# PCB_Schematic_Smart_Home.net
KiCad netlist of a schematic drawn in EasyEDA
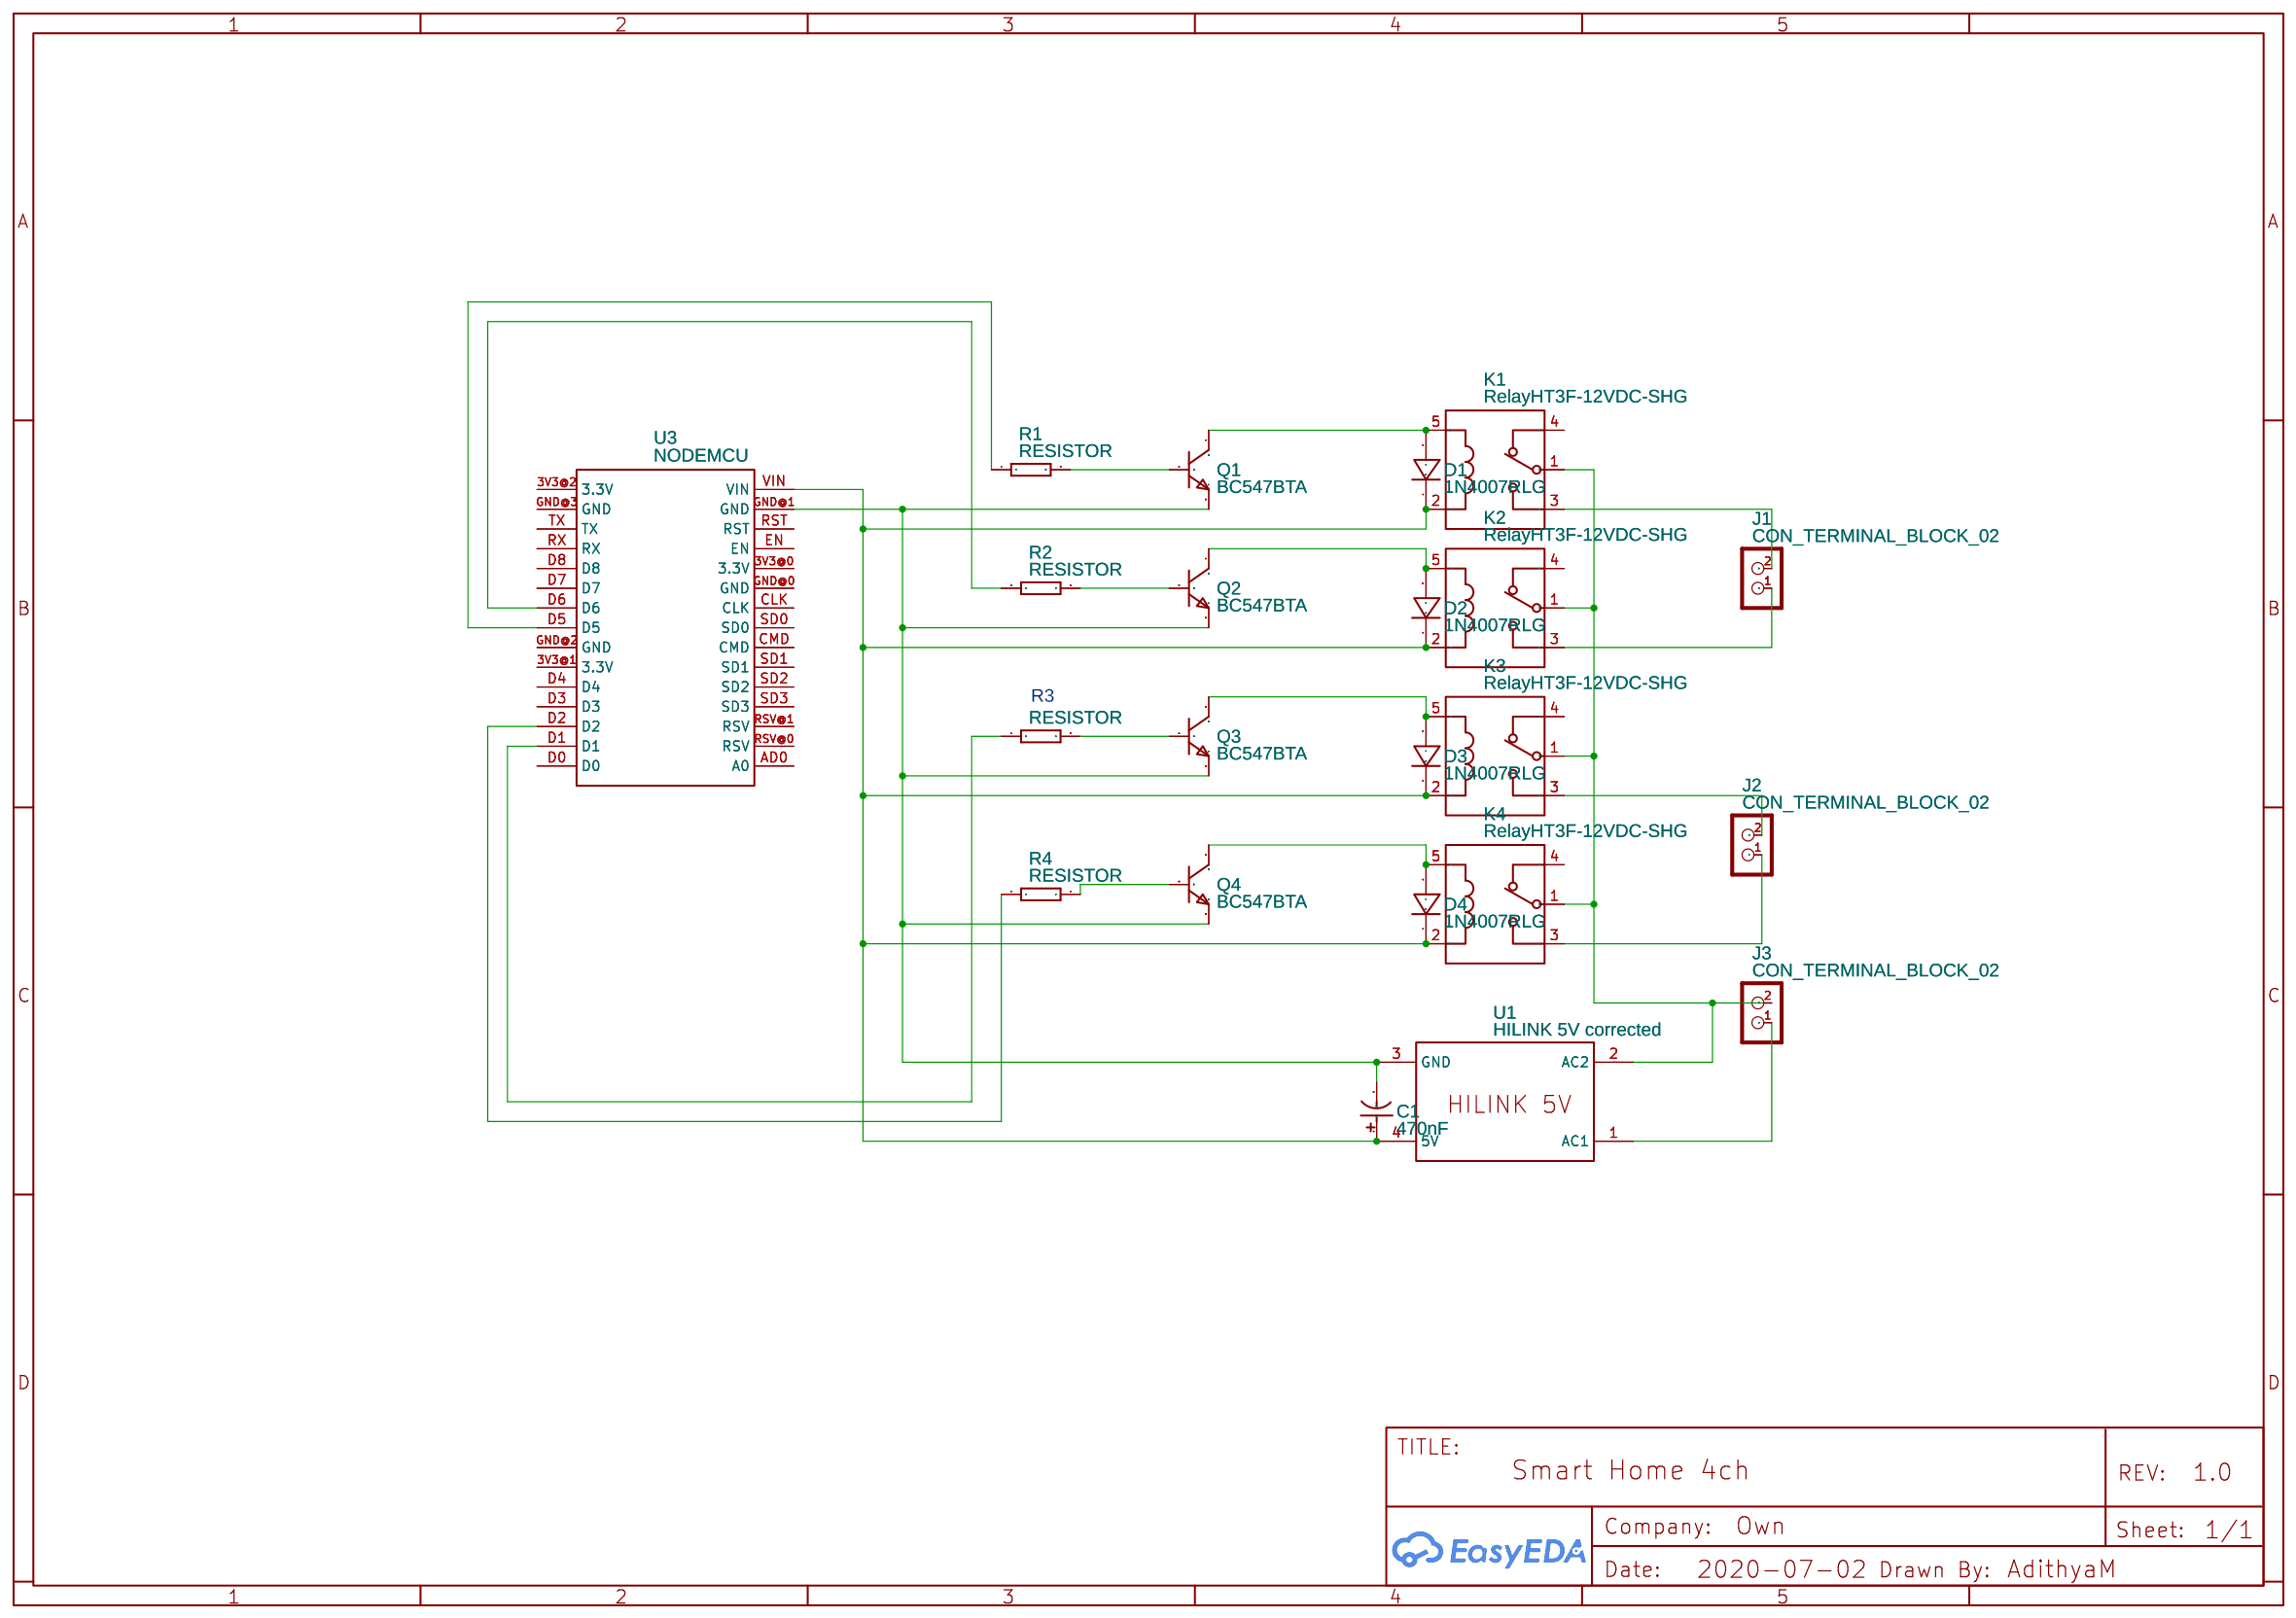
[diagram p0: schematic sheet]

(export (version "E")
  (design (tool "Eeschema 10.0.6"))
  (components
    (comp (ref "C1")
      (value "470nF")
      (fields
        (field (name "BOM_Manufacturer Part") "0.47uF 50V 4*5")
        (field (name "BOM_Supplier Part") "C45095")
      )
      (libsource (lib "") (part "0.47uF_50V_mz"))
    )
    (comp (ref "D1")
      (value "1N4007RLG")
      (fields (field (name "BOM_Supplier Part") "C53568"))
      (libsource (lib "") (part "1N4007RLG"))
    )
    (comp (ref "D2")
      (value "1N4007RLG")
      (fields (field (name "BOM_Supplier Part") "C53568"))
      (libsource (lib "") (part "1N4007RLG"))
    )
    (comp (ref "D3")
      (value "1N4007RLG")
      (fields (field (name "BOM_Supplier Part") "C53568"))
      (libsource (lib "") (part "1N4007RLG"))
    )
    (comp (ref "D4")
      (value "1N4007RLG")
      (fields (field (name "BOM_Supplier Part") "C53568"))
      (libsource (lib "") (part "1N4007RLG"))
    )
    (comp (ref "J1") (value "CON_TERMINAL_BLOCK_02") (libsource (lib "") (part "CON_TERMINAL_BLOCK_02")))
    (comp (ref "J2") (value "CON_TERMINAL_BLOCK_02") (libsource (lib "") (part "CON_TERMINAL_BLOCK_02")))
    (comp (ref "J3") (value "CON_TERMINAL_BLOCK_02") (libsource (lib "") (part "CON_TERMINAL_BLOCK_02")))
    (comp (ref "K1")
      (value "RelayHT3F-12VDC-SHG")
      (fields (field (name "BOM_Supplier Part") "C22022"))
      (libsource (lib "") (part "RelayHT3F-12VDC-SHG"))
    )
    (comp (ref "K2")
      (value "RelayHT3F-12VDC-SHG")
      (fields (field (name "BOM_Supplier Part") "C22022"))
      (libsource (lib "") (part "RelayHT3F-12VDC-SHG"))
    )
    (comp (ref "K3")
      (value "RelayHT3F-12VDC-SHG")
      (fields (field (name "BOM_Supplier Part") "C22022"))
      (libsource (lib "") (part "RelayHT3F-12VDC-SHG"))
    )
    (comp (ref "K4")
      (value "RelayHT3F-12VDC-SHG")
      (fields (field (name "BOM_Supplier Part") "C22022"))
      (libsource (lib "") (part "RelayHT3F-12VDC-SHG"))
    )
    (comp (ref "Q1")
      (value "BC547BTA")
      (fields (field (name "BOM_Supplier Part") "C258144"))
      (libsource (lib "") (part "BC547BTA"))
    )
    (comp (ref "Q2")
      (value "BC547BTA")
      (fields (field (name "BOM_Supplier Part") "C258144"))
      (libsource (lib "") (part "BC547BTA"))
    )
    (comp (ref "Q3")
      (value "BC547BTA")
      (fields (field (name "BOM_Supplier Part") "C258144"))
      (libsource (lib "") (part "BC547BTA"))
    )
    (comp (ref "Q4")
      (value "BC547BTA")
      (fields (field (name "BOM_Supplier Part") "C258144"))
      (libsource (lib "") (part "BC547BTA"))
    )
    (comp (ref "R1") (value "RESISTOR") (libsource (lib "") (part "RESISTOR")))
    (comp (ref "R2") (value "RESISTOR") (libsource (lib "") (part "RESISTOR")))
    (comp (ref "R3") (value "RESISTOR") (libsource (lib "") (part "RESISTOR")))
    (comp (ref "R4") (value "RESISTOR") (libsource (lib "") (part "RESISTOR")))
    (comp (ref "U1")
      (value "HILINK 5V corrected")
      (fields (field (name "BOM_Manufacturer Part") "HILINK 5V"))
      (libsource (lib "") (part "HILINK 5V corrected"))
    )
    (comp (ref "U3") (value "NODEMCU") (libsource (lib "") (part "NODEMCU")))
  )
  (nets
    (net (code "1") (name "Net-(D1-A)") (class "Default")
      (node (ref "D1") (pin "2") (pinfunction "A_2") (pintype "unspecified"))
      (node (ref "K1") (pin "5") (pinfunction "5_5") (pintype "unspecified"))
      (node (ref "Q1") (pin "1") (pinfunction "C_1") (pintype "unspecified"))
    )
    (net (code "2") (name "Net-(D1-C)") (class "Default")
      (node (ref "C1") (pin "1") (pinfunction "1_1") (pintype "input"))
      (node (ref "D1") (pin "1") (pinfunction "C_1") (pintype "unspecified"))
      (node (ref "D2") (pin "1") (pinfunction "C_1") (pintype "unspecified"))
      (node (ref "D3") (pin "1") (pinfunction "C_1") (pintype "unspecified"))
      (node (ref "D4") (pin "1") (pinfunction "C_1") (pintype "unspecified"))
      (node (ref "K1") (pin "2") (pinfunction "2_2") (pintype "unspecified"))
      (node (ref "K2") (pin "2") (pinfunction "2_2") (pintype "unspecified"))
      (node (ref "K3") (pin "2") (pinfunction "2_2") (pintype "unspecified"))
      (node (ref "K4") (pin "2") (pinfunction "2_2") (pintype "unspecified"))
      (node (ref "U1") (pin "4") (pinfunction "5V_4") (pintype "unspecified"))
      (node (ref "U3") (pin "VIN") (pinfunction "VIN_VIN") (pintype "unspecified"))
    )
    (net (code "3") (name "Net-(D2-A)") (class "Default")
      (node (ref "D2") (pin "2") (pinfunction "A_2") (pintype "unspecified"))
      (node (ref "K2") (pin "5") (pinfunction "5_5") (pintype "unspecified"))
      (node (ref "Q2") (pin "1") (pinfunction "C_1") (pintype "unspecified"))
    )
    (net (code "4") (name "Net-(D3-A)") (class "Default")
      (node (ref "D3") (pin "2") (pinfunction "A_2") (pintype "unspecified"))
      (node (ref "K3") (pin "5") (pinfunction "5_5") (pintype "unspecified"))
      (node (ref "Q3") (pin "1") (pinfunction "C_1") (pintype "unspecified"))
    )
    (net (code "5") (name "Net-(D4-A)") (class "Default")
      (node (ref "D4") (pin "2") (pinfunction "A_2") (pintype "unspecified"))
      (node (ref "K4") (pin "5") (pinfunction "5_5") (pintype "unspecified"))
      (node (ref "Q4") (pin "1") (pinfunction "C_1") (pintype "unspecified"))
    )
    (net (code "6") (name "Net-(J1-Pad1)") (class "Default")
      (node (ref "J1") (pin "1") (pinfunction "1_1") (pintype "unspecified"))
      (node (ref "K2") (pin "3") (pinfunction "3_3") (pintype "unspecified"))
    )
    (net (code "7") (name "Net-(J1-Pad2)") (class "Default")
      (node (ref "J1") (pin "2") (pinfunction "2_2") (pintype "unspecified"))
      (node (ref "K1") (pin "3") (pinfunction "3_3") (pintype "unspecified"))
    )
    (net (code "8") (name "Net-(J2-Pad1)") (class "Default")
      (node (ref "J2") (pin "1") (pinfunction "1_1") (pintype "unspecified"))
      (node (ref "K4") (pin "3") (pinfunction "3_3") (pintype "unspecified"))
    )
    (net (code "9") (name "Net-(J2-Pad2)") (class "Default")
      (node (ref "J2") (pin "2") (pinfunction "2_2") (pintype "unspecified"))
      (node (ref "K3") (pin "3") (pinfunction "3_3") (pintype "unspecified"))
    )
    (net (code "10") (name "Net-(Q1-B)") (class "Default")
      (node (ref "Q1") (pin "2") (pinfunction "B_2") (pintype "unspecified"))
      (node (ref "R1") (pin "2") (pinfunction "2_2") (pintype "unspecified"))
    )
    (net (code "11") (name "Net-(Q1-E)") (class "Default")
      (node (ref "C1") (pin "2") (pinfunction "2_2") (pintype "input"))
      (node (ref "Q1") (pin "3") (pinfunction "E_3") (pintype "unspecified"))
      (node (ref "Q2") (pin "3") (pinfunction "E_3") (pintype "unspecified"))
      (node (ref "Q3") (pin "3") (pinfunction "E_3") (pintype "unspecified"))
      (node (ref "Q4") (pin "3") (pinfunction "E_3") (pintype "unspecified"))
      (node (ref "U1") (pin "3") (pinfunction "GND_3") (pintype "unspecified"))
      (node (ref "U3") (pin "GND@1") (pinfunction "GND_GND@1") (pintype "unspecified"))
    )
    (net (code "12") (name "Net-(Q2-B)") (class "Default")
      (node (ref "Q2") (pin "2") (pinfunction "B_2") (pintype "unspecified"))
      (node (ref "R2") (pin "2") (pinfunction "2_2") (pintype "unspecified"))
    )
    (net (code "13") (name "Net-(Q3-B)") (class "Default")
      (node (ref "Q3") (pin "2") (pinfunction "B_2") (pintype "unspecified"))
      (node (ref "R3") (pin "2") (pinfunction "2_2") (pintype "unspecified"))
    )
    (net (code "14") (name "Net-(Q4-B)") (class "Default")
      (node (ref "Q4") (pin "2") (pinfunction "B_2") (pintype "unspecified"))
      (node (ref "R4") (pin "2") (pinfunction "2_2") (pintype "unspecified"))
    )
    (net (code "15") (name "Net-(R1-Pad1)") (class "Default")
      (node (ref "R1") (pin "1") (pinfunction "1_1") (pintype "unspecified"))
      (node (ref "U3") (pin "D5") (pinfunction "D5_D5") (pintype "unspecified"))
    )
    (net (code "16") (name "Net-(R2-Pad1)") (class "Default")
      (node (ref "R2") (pin "1") (pinfunction "1_1") (pintype "unspecified"))
      (node (ref "U3") (pin "D6") (pinfunction "D6_D6") (pintype "unspecified"))
    )
    (net (code "17") (name "Net-(R3-Pad1)") (class "Default")
      (node (ref "R3") (pin "1") (pinfunction "1_1") (pintype "unspecified"))
      (node (ref "U3") (pin "D1") (pinfunction "D1_D1") (pintype "unspecified"))
    )
    (net (code "18") (name "Net-(R4-Pad1)") (class "Default")
      (node (ref "R4") (pin "1") (pinfunction "1_1") (pintype "unspecified"))
      (node (ref "U3") (pin "D2") (pinfunction "D2_D2") (pintype "unspecified"))
    )
    (net (code "19") (name "Net-(U1-AC1)") (class "Default")
      (node (ref "J3") (pin "1") (pinfunction "1_1") (pintype "unspecified"))
      (node (ref "U1") (pin "1") (pinfunction "AC1_1") (pintype "unspecified"))
    )
    (net (code "20") (name "Net-(U1-AC2)") (class "Default")
      (node (ref "J3") (pin "2") (pinfunction "2_2") (pintype "unspecified"))
      (node (ref "K1") (pin "1") (pinfunction "1_1") (pintype "unspecified"))
      (node (ref "K2") (pin "1") (pinfunction "1_1") (pintype "unspecified"))
      (node (ref "K3") (pin "1") (pinfunction "1_1") (pintype "unspecified"))
      (node (ref "K4") (pin "1") (pinfunction "1_1") (pintype "unspecified"))
      (node (ref "U1") (pin "2") (pinfunction "AC2_2") (pintype "unspecified"))
    )
    (net (code "21") (name "unconnected-(K1-Pad4)") (class "Default")
      (node (ref "K1") (pin "4") (pinfunction "4_4") (pintype "unspecified"))
    )
    (net (code "22") (name "unconnected-(K2-Pad4)") (class "Default")
      (node (ref "K2") (pin "4") (pinfunction "4_4") (pintype "unspecified"))
    )
    (net (code "23") (name "unconnected-(K3-Pad4)") (class "Default")
      (node (ref "K3") (pin "4") (pinfunction "4_4") (pintype "unspecified"))
    )
    (net (code "24") (name "unconnected-(K4-Pad4)") (class "Default")
      (node (ref "K4") (pin "4") (pinfunction "4_4") (pintype "unspecified"))
    )
    (net (code "25") (name "unconnected-(U3-3.3V-Pad3V3@0)") (class "Default")
      (node (ref "U3") (pin "3V3@0") (pinfunction "3.3V_3V3@0") (pintype "unspecified"))
    )
    (net (code "26") (name "unconnected-(U3-3.3V-Pad3V3@1)") (class "Default")
      (node (ref "U3") (pin "3V3@1") (pinfunction "3.3V_3V3@1") (pintype "unspecified"))
    )
    (net (code "27") (name "unconnected-(U3-3.3V-Pad3V3@2)") (class "Default")
      (node (ref "U3") (pin "3V3@2") (pinfunction "3.3V_3V3@2") (pintype "unspecified"))
    )
    (net (code "28") (name "unconnected-(U3-A0-PadAD0)") (class "Default")
      (node (ref "U3") (pin "AD0") (pinfunction "A0_AD0") (pintype "unspecified"))
    )
    (net (code "29") (name "unconnected-(U3-GND-PadGND@0)") (class "Default")
      (node (ref "U3") (pin "GND@0") (pinfunction "GND_GND@0") (pintype "unspecified"))
    )
    (net (code "30") (name "unconnected-(U3-GND-PadGND@2)") (class "Default")
      (node (ref "U3") (pin "GND@2") (pinfunction "GND_GND@2") (pintype "unspecified"))
    )
    (net (code "31") (name "unconnected-(U3-GND-PadGND@3)") (class "Default")
      (node (ref "U3") (pin "GND@3") (pinfunction "GND_GND@3") (pintype "unspecified"))
    )
    (net (code "32") (name "unconnected-(U3-PadCLK)") (class "Default")
      (node (ref "U3") (pin "CLK") (pinfunction "CLK_CLK") (pintype "unspecified"))
    )
    (net (code "33") (name "unconnected-(U3-PadCMD)") (class "Default")
      (node (ref "U3") (pin "CMD") (pinfunction "CMD_CMD") (pintype "unspecified"))
    )
    (net (code "34") (name "unconnected-(U3-PadD0)") (class "Default")
      (node (ref "U3") (pin "D0") (pinfunction "D0_D0") (pintype "unspecified"))
    )
    (net (code "35") (name "unconnected-(U3-PadD3)") (class "Default")
      (node (ref "U3") (pin "D3") (pinfunction "D3_D3") (pintype "unspecified"))
    )
    (net (code "36") (name "unconnected-(U3-PadD4)") (class "Default")
      (node (ref "U3") (pin "D4") (pinfunction "D4_D4") (pintype "unspecified"))
    )
    (net (code "37") (name "unconnected-(U3-PadD7)") (class "Default")
      (node (ref "U3") (pin "D7") (pinfunction "D7_D7") (pintype "unspecified"))
    )
    (net (code "38") (name "unconnected-(U3-PadD8)") (class "Default")
      (node (ref "U3") (pin "D8") (pinfunction "D8_D8") (pintype "unspecified"))
    )
    (net (code "39") (name "unconnected-(U3-PadEN)") (class "Default")
      (node (ref "U3") (pin "EN") (pinfunction "EN_EN") (pintype "unspecified"))
    )
    (net (code "40") (name "unconnected-(U3-PadRST)") (class "Default")
      (node (ref "U3") (pin "RST") (pinfunction "RST_RST") (pintype "unspecified"))
    )
    (net (code "41") (name "unconnected-(U3-PadRX)") (class "Default")
      (node (ref "U3") (pin "RX") (pinfunction "RX_RX") (pintype "unspecified"))
    )
    (net (code "42") (name "unconnected-(U3-PadSD0)") (class "Default")
      (node (ref "U3") (pin "SD0") (pinfunction "SD0_SD0") (pintype "unspecified"))
    )
    (net (code "43") (name "unconnected-(U3-PadSD1)") (class "Default")
      (node (ref "U3") (pin "SD1") (pinfunction "SD1_SD1") (pintype "unspecified"))
    )
    (net (code "44") (name "unconnected-(U3-PadSD2)") (class "Default")
      (node (ref "U3") (pin "SD2") (pinfunction "SD2_SD2") (pintype "unspecified"))
    )
    (net (code "45") (name "unconnected-(U3-PadSD3)") (class "Default")
      (node (ref "U3") (pin "SD3") (pinfunction "SD3_SD3") (pintype "unspecified"))
    )
    (net (code "46") (name "unconnected-(U3-PadTX)") (class "Default")
      (node (ref "U3") (pin "TX") (pinfunction "TX_TX") (pintype "unspecified"))
    )
    (net (code "47") (name "unconnected-(U3-RSV-PadRSV@0)") (class "Default")
      (node (ref "U3") (pin "RSV@0") (pinfunction "RSV_RSV@0") (pintype "unspecified"))
    )
    (net (code "48") (name "unconnected-(U3-RSV-PadRSV@1)") (class "Default")
      (node (ref "U3") (pin "RSV@1") (pinfunction "RSV_RSV@1") (pintype "unspecified"))
    )
  )
)
